# LCD_Breakout.net
KiCad netlist of a schematic drawn in EAGLE
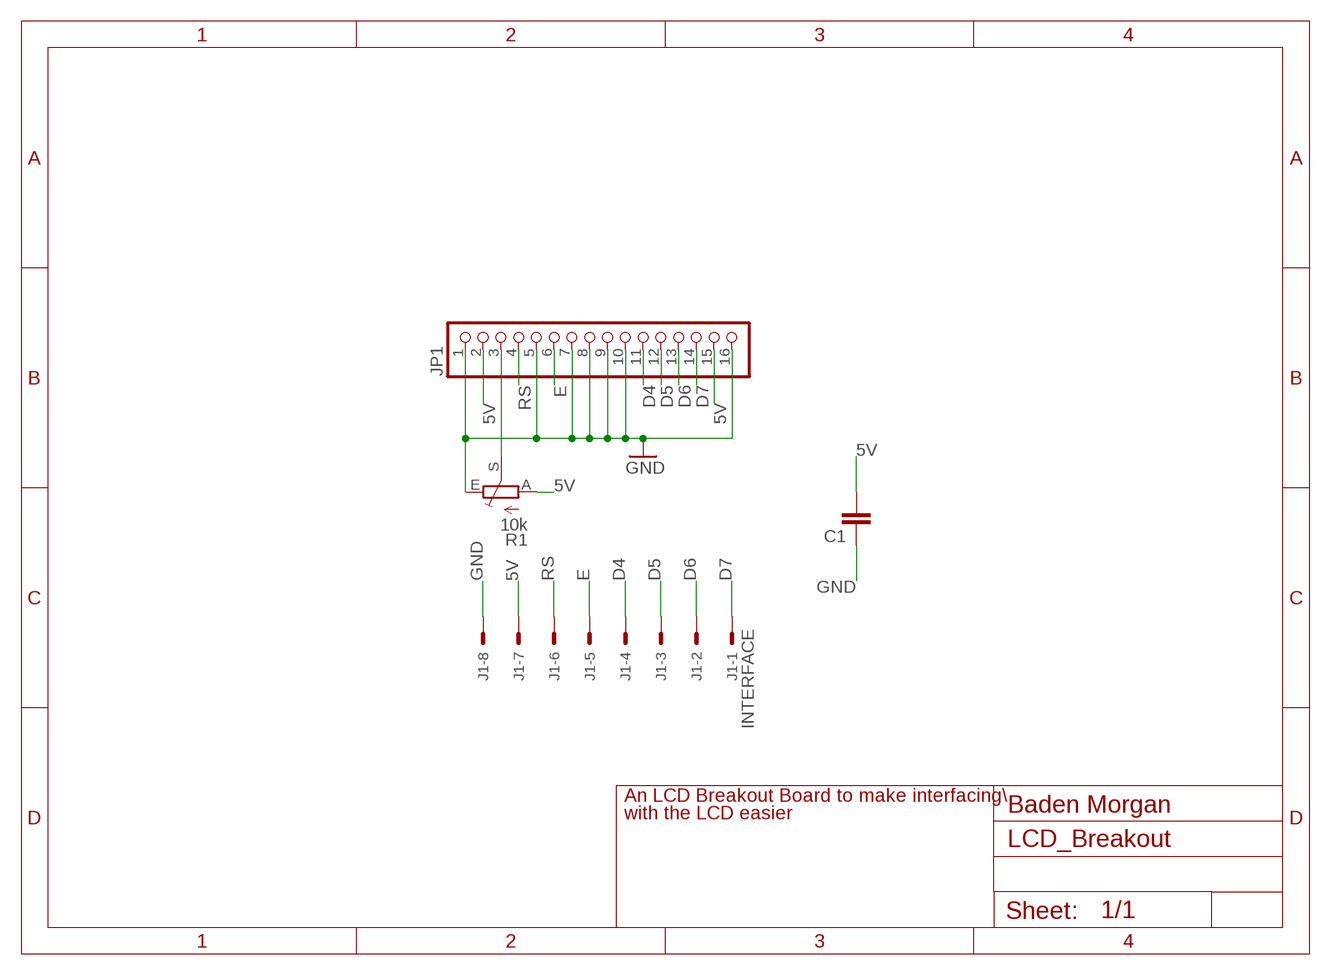
[diagram p0: schematic, sheet 1]

(export (version "E")
  (design (tool "Eeschema 10.0.6"))
  (components
    (comp (ref "C1")
      (value "C5/2.5")
      (footprint "eagle-import:C5B2.5")
      (libsource (lib "eagle-import") (part "C5/2.5"))
    )
    (comp (ref "J1")
      (value "INTERFACE")
      (footprint "eagle-import:7395-08")
      (libsource (lib "eagle-import") (part "22-?-0805-7088"))
    )
    (comp (ref "JP1")
      (value "PINHD-1X16")
      (footprint "eagle-import:1X16")
      (libsource (lib "eagle-import") (part "PINHD-1X16"))
    )
    (comp (ref "R1")
      (value "10k")
      (footprint "eagle-import:CA6V")
      (libsource (lib "eagle-import") (part "TRIM_EU-CA6V"))
    )
  )
  (nets
    (net (code "1") (name "/5V") (class "Default")
      (node (ref "C1") (pin "2") (pinfunction "2_2") (pintype "passive"))
      (node (ref "J1") (pin "7") (pinfunction "S_7") (pintype "passive"))
      (node (ref "JP1") (pin "15") (pinfunction "15_15") (pintype "passive"))
      (node (ref "JP1") (pin "2") (pinfunction "2_2") (pintype "passive"))
      (node (ref "R1") (pin "A") (pinfunction "A_A") (pintype "passive"))
    )
    (net (code "2") (name "/D4") (class "Default")
      (node (ref "J1") (pin "4") (pinfunction "S_4") (pintype "passive"))
      (node (ref "JP1") (pin "11") (pinfunction "11_11") (pintype "passive"))
    )
    (net (code "3") (name "/D5") (class "Default")
      (node (ref "J1") (pin "3") (pinfunction "S_3") (pintype "passive"))
      (node (ref "JP1") (pin "12") (pinfunction "12_12") (pintype "passive"))
    )
    (net (code "4") (name "/D6") (class "Default")
      (node (ref "J1") (pin "2") (pinfunction "S_2") (pintype "passive"))
      (node (ref "JP1") (pin "13") (pinfunction "13_13") (pintype "passive"))
    )
    (net (code "5") (name "/D7") (class "Default")
      (node (ref "J1") (pin "1") (pinfunction "S_1") (pintype "passive"))
      (node (ref "JP1") (pin "14") (pinfunction "14_14") (pintype "passive"))
    )
    (net (code "6") (name "/E") (class "Default")
      (node (ref "J1") (pin "5") (pinfunction "S_5") (pintype "passive"))
      (node (ref "JP1") (pin "6") (pinfunction "6_6") (pintype "passive"))
    )
    (net (code "7") (name "/RS") (class "Default")
      (node (ref "J1") (pin "6") (pinfunction "S_6") (pintype "passive"))
      (node (ref "JP1") (pin "4") (pinfunction "4_4") (pintype "passive"))
    )
    (net (code "8") (name "GND") (class "Default")
      (node (ref "C1") (pin "1") (pinfunction "1_1") (pintype "passive"))
      (node (ref "J1") (pin "8") (pinfunction "S_8") (pintype "passive"))
      (node (ref "JP1") (pin "1") (pinfunction "1_1") (pintype "passive"))
      (node (ref "JP1") (pin "10") (pinfunction "10_10") (pintype "passive"))
      (node (ref "JP1") (pin "16") (pinfunction "16_16") (pintype "passive"))
      (node (ref "JP1") (pin "5") (pinfunction "5_5") (pintype "passive"))
      (node (ref "JP1") (pin "7") (pinfunction "7_7") (pintype "passive"))
      (node (ref "JP1") (pin "8") (pinfunction "8_8") (pintype "passive"))
      (node (ref "JP1") (pin "9") (pinfunction "9_9") (pintype "passive"))
      (node (ref "R1") (pin "E") (pinfunction "E_E") (pintype "passive"))
    )
    (net (code "9") (name "Net-(JP1-Pad3)") (class "Default")
      (node (ref "JP1") (pin "3") (pinfunction "3_3") (pintype "passive"))
      (node (ref "R1") (pin "S") (pinfunction "S_S") (pintype "passive"))
    )
  )
)
